# PCBDesign.net
KiCad netlist of a schematic drawn in EAGLE
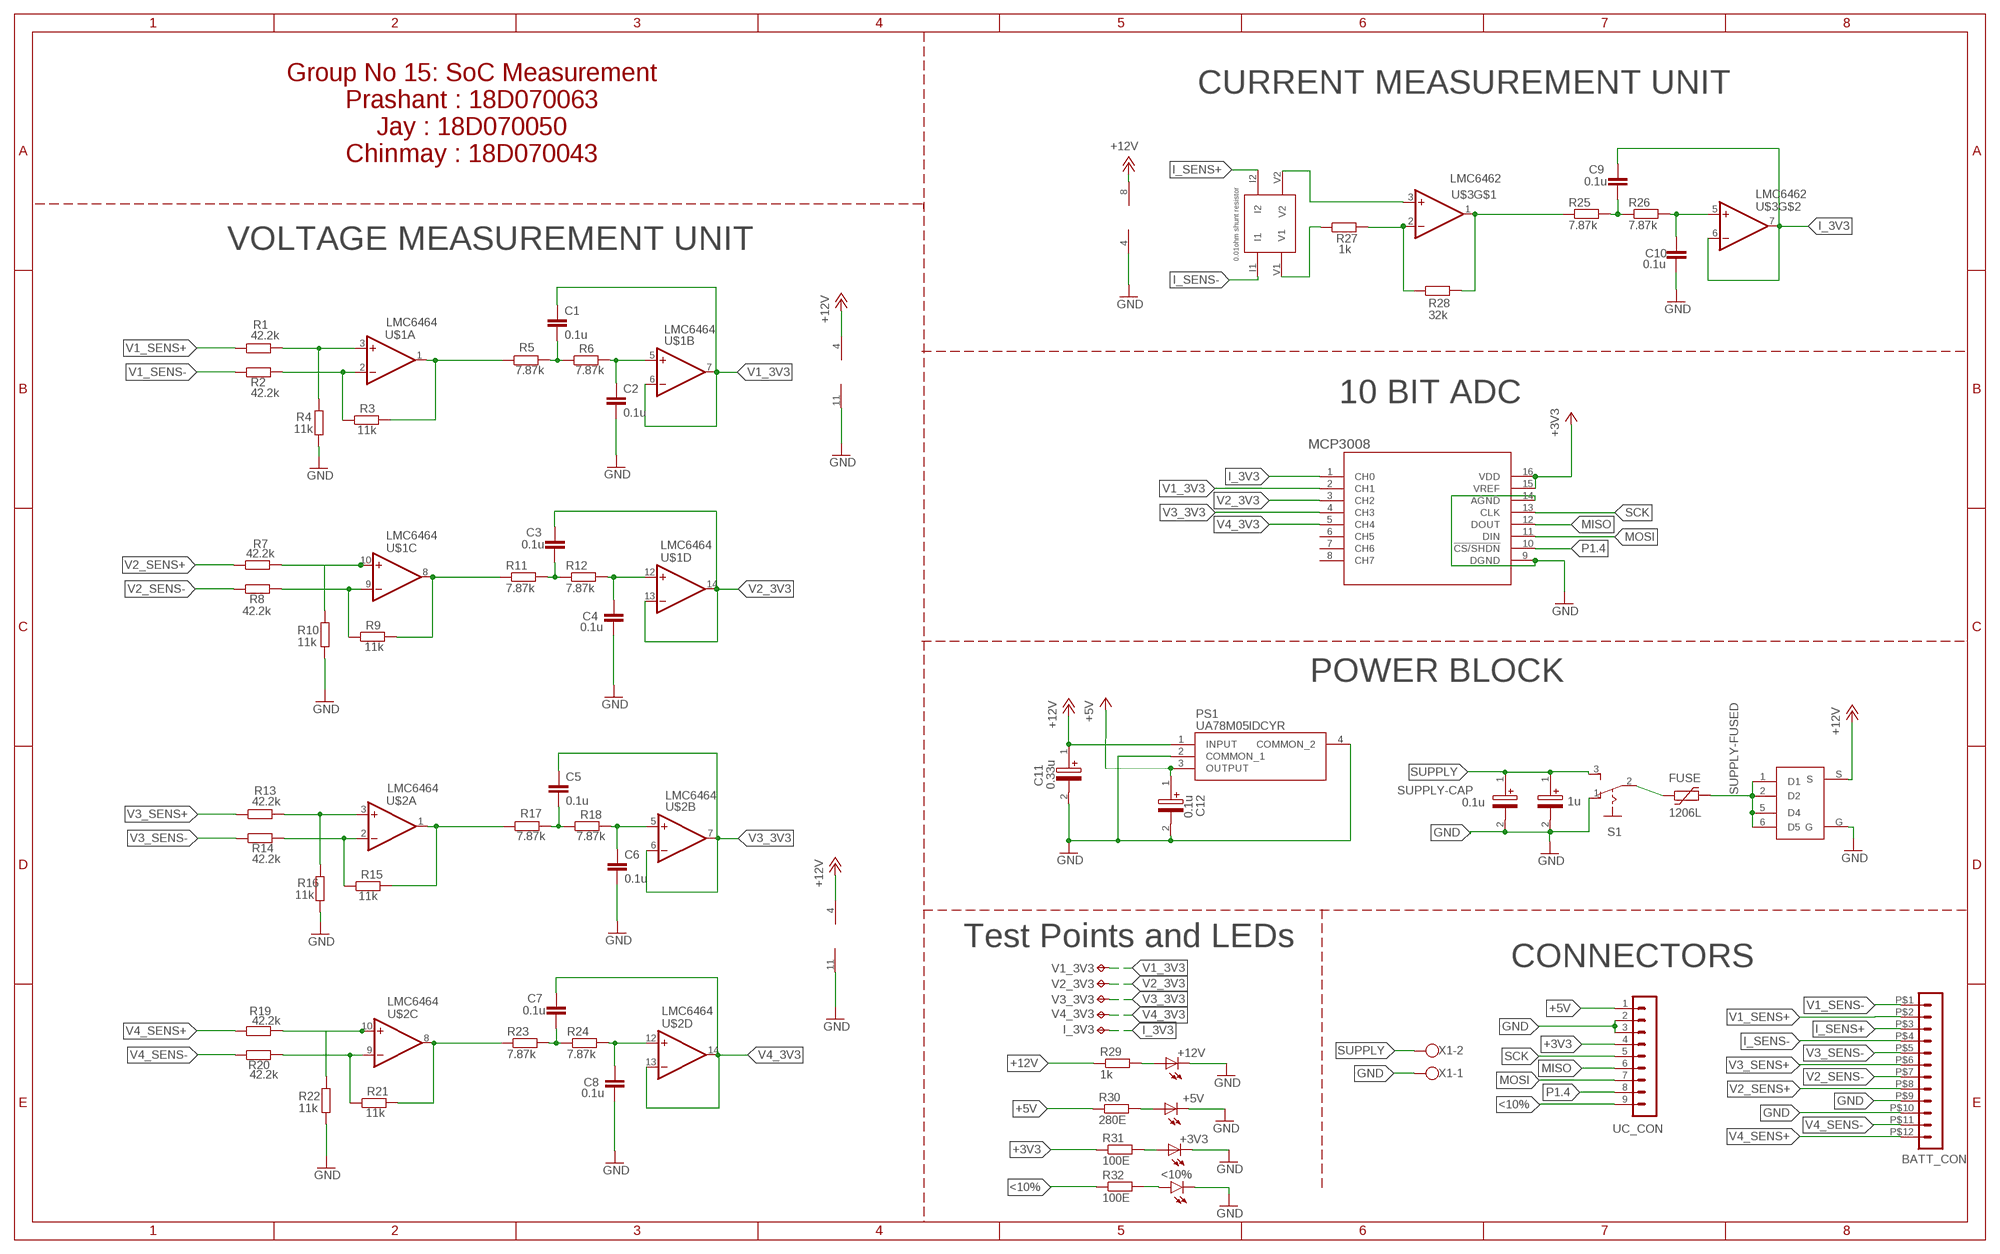
[diagram p0: schematic, sheet 1]

(export (version "E")
  (design (tool "Eeschema 10.0.6"))
  (components
    (comp (ref "+3V3")
      (value "LED-FKIT-1206")
      (footprint "eagle-import:FKIT-LED-1206")
      (libsource (lib "eagle-import") (part "LED-FKIT-1206"))
    )
    (comp (ref "+5V")
      (value "LED-FKIT-1206")
      (footprint "eagle-import:FKIT-LED-1206")
      (libsource (lib "eagle-import") (part "LED-FKIT-1206"))
    )
    (comp (ref "+12V")
      (value "LED-FKIT-1206")
      (footprint "eagle-import:FKIT-LED-1206")
      (libsource (lib "eagle-import") (part "LED-FKIT-1206"))
    )
    (comp (ref "<10%")
      (value "LED5MM")
      (footprint "eagle-import:LED5MM")
      (libsource (lib "eagle-import") (part "led_259_LED5MM"))
    )
    (comp (ref "BATT_CON")
      (value "HEADER_POS12_43045-1212")
      (footprint "eagle-import:43045-1212")
      (libsource (lib "eagle-import") (part "HEADER_POS12_?43045-1212"))
    )
    (comp (ref "C1")
      (value "0.1u")
      (footprint "eagle-import:C0805")
      (libsource (lib "eagle-import") (part "C-EUC0805"))
    )
    (comp (ref "C2")
      (value "0.1u")
      (footprint "eagle-import:C0805")
      (libsource (lib "eagle-import") (part "C-EUC0805"))
    )
    (comp (ref "C3")
      (value "0.1u")
      (footprint "eagle-import:C0805")
      (libsource (lib "eagle-import") (part "C-EUC0805"))
    )
    (comp (ref "C4")
      (value "0.1u")
      (footprint "eagle-import:C0805")
      (libsource (lib "eagle-import") (part "C-EUC0805"))
    )
    (comp (ref "C5")
      (value "0.1u")
      (footprint "eagle-import:C0805")
      (libsource (lib "eagle-import") (part "C-EUC0805"))
    )
    (comp (ref "C6")
      (value "0.1u")
      (footprint "eagle-import:C0805")
      (libsource (lib "eagle-import") (part "C-EUC0805"))
    )
    (comp (ref "C7")
      (value "0.1u")
      (footprint "eagle-import:C0805")
      (libsource (lib "eagle-import") (part "C-EUC0805"))
    )
    (comp (ref "C8")
      (value "0.1u")
      (footprint "eagle-import:C0805")
      (libsource (lib "eagle-import") (part "C-EUC0805"))
    )
    (comp (ref "C9")
      (value "0.1u")
      (footprint "eagle-import:C0805")
      (libsource (lib "eagle-import") (part "C-EUC0805"))
    )
    (comp (ref "C10")
      (value "0.1u")
      (footprint "eagle-import:C0805")
      (libsource (lib "eagle-import") (part "C-EUC0805"))
    )
    (comp (ref "C11")
      (value "0.33u")
      (footprint "eagle-import:CAPPM2014X120N")
      (fields
        (field (name "MANUFACTURER_PART_NUMBER") "TAJR334K020RNJ")
        (field (name "MOUSER_PART_NUMBER") "581-TAJR334K020R")
      )
      (libsource (lib "eagle-import") (part "TAJR334K020RNJ"))
    )
    (comp (ref "C12")
      (value "0.1u")
      (footprint "eagle-import:CAPPM2014X120N")
      (fields
        (field (name "MANUFACTURER_PART_NUMBER") "TAJR334K020RNJ")
        (field (name "MOUSER_PART_NUMBER") "581-TAJR334K020R")
      )
      (libsource (lib "eagle-import") (part "TAJR334K020RNJ"))
    )
    (comp (ref "FUSE")
      (value "1206L")
      (footprint "eagle-import:1206L")
      (fields (field (name "MFR") "Littelfuse"))
      (libsource (lib "eagle-import") (part "1206L"))
    )
    (comp (ref "I_3V3")
      (value "TESTPADPAD1-13")
      (footprint "eagle-import:P1-13")
      (libsource (lib "eagle-import") (part "TESTPADPAD1-13"))
    )
    (comp (ref "PS1")
      (value "UA78M05IDCYR")
      (footprint "eagle-import:SOT230P700X180-4N")
      (fields (field (name "MOUSER_PART_NUMBER") "595-UA78M05IDCYR"))
      (libsource (lib "eagle-import") (part "UA78M05IDCYR"))
    )
    (comp (ref "R1")
      (value "42.2k")
      (footprint "eagle-import:R0805")
      (libsource (lib "eagle-import") (part "IIT_BOMBAY_Racing2_R-EU_R0805"))
    )
    (comp (ref "R2")
      (value "42.2k")
      (footprint "eagle-import:R0805")
      (libsource (lib "eagle-import") (part "IIT_BOMBAY_Racing2_R-EU_R0805"))
    )
    (comp (ref "R3")
      (value "11k")
      (footprint "eagle-import:R0805")
      (libsource (lib "eagle-import") (part "IIT_BOMBAY_Racing2_R-EU_R0805"))
    )
    (comp (ref "R4")
      (value "11k")
      (footprint "eagle-import:R0805")
      (libsource (lib "eagle-import") (part "IIT_BOMBAY_Racing2_R-EU_R0805"))
    )
    (comp (ref "R5")
      (value "7.87k")
      (footprint "eagle-import:R0805")
      (libsource (lib "eagle-import") (part "IIT_BOMBAY_Racing2_R-EU_R0805"))
    )
    (comp (ref "R6")
      (value "7.87k")
      (footprint "eagle-import:R0805")
      (libsource (lib "eagle-import") (part "IIT_BOMBAY_Racing2_R-EU_R0805"))
    )
    (comp (ref "R7")
      (value "42.2k")
      (footprint "eagle-import:R0805")
      (libsource (lib "eagle-import") (part "IIT_BOMBAY_Racing2_R-EU_R0805"))
    )
    (comp (ref "R8")
      (value "42.2k")
      (footprint "eagle-import:R0805")
      (libsource (lib "eagle-import") (part "IIT_BOMBAY_Racing2_R-EU_R0805"))
    )
    (comp (ref "R9")
      (value "11k")
      (footprint "eagle-import:R0805")
      (libsource (lib "eagle-import") (part "IIT_BOMBAY_Racing2_R-EU_R0805"))
    )
    (comp (ref "R10")
      (value "11k")
      (footprint "eagle-import:R0805")
      (libsource (lib "eagle-import") (part "IIT_BOMBAY_Racing2_R-EU_R0805"))
    )
    (comp (ref "R11")
      (value "7.87k")
      (footprint "eagle-import:R0805")
      (libsource (lib "eagle-import") (part "IIT_BOMBAY_Racing2_R-EU_R0805"))
    )
    (comp (ref "R12")
      (value "7.87k")
      (footprint "eagle-import:R0805")
      (libsource (lib "eagle-import") (part "IIT_BOMBAY_Racing2_R-EU_R0805"))
    )
    (comp (ref "R13")
      (value "42.2k")
      (footprint "eagle-import:R0805")
      (libsource (lib "eagle-import") (part "IIT_BOMBAY_Racing2_R-EU_R0805"))
    )
    (comp (ref "R14")
      (value "42.2k")
      (footprint "eagle-import:R0805")
      (libsource (lib "eagle-import") (part "IIT_BOMBAY_Racing2_R-EU_R0805"))
    )
    (comp (ref "R15")
      (value "11k")
      (footprint "eagle-import:R0805")
      (libsource (lib "eagle-import") (part "IIT_BOMBAY_Racing2_R-EU_R0805"))
    )
    (comp (ref "R16")
      (value "11k")
      (footprint "eagle-import:R0805")
      (libsource (lib "eagle-import") (part "IIT_BOMBAY_Racing2_R-EU_R0805"))
    )
    (comp (ref "R17")
      (value "7.87k")
      (footprint "eagle-import:R0805")
      (libsource (lib "eagle-import") (part "IIT_BOMBAY_Racing2_R-EU_R0805"))
    )
    (comp (ref "R18")
      (value "7.87k")
      (footprint "eagle-import:R0805")
      (libsource (lib "eagle-import") (part "IIT_BOMBAY_Racing2_R-EU_R0805"))
    )
    (comp (ref "R19")
      (value "42.2k")
      (footprint "eagle-import:R0805")
      (libsource (lib "eagle-import") (part "IIT_BOMBAY_Racing2_R-EU_R0805"))
    )
    (comp (ref "R20")
      (value "42.2k")
      (footprint "eagle-import:R0805")
      (libsource (lib "eagle-import") (part "IIT_BOMBAY_Racing2_R-EU_R0805"))
    )
    (comp (ref "R21")
      (value "11k")
      (footprint "eagle-import:R0805")
      (libsource (lib "eagle-import") (part "IIT_BOMBAY_Racing2_R-EU_R0805"))
    )
    (comp (ref "R22")
      (value "11k")
      (footprint "eagle-import:R0805")
      (libsource (lib "eagle-import") (part "IIT_BOMBAY_Racing2_R-EU_R0805"))
    )
    (comp (ref "R23")
      (value "7.87k")
      (footprint "eagle-import:R0805")
      (libsource (lib "eagle-import") (part "IIT_BOMBAY_Racing2_R-EU_R0805"))
    )
    (comp (ref "R24")
      (value "7.87k")
      (footprint "eagle-import:R0805")
      (libsource (lib "eagle-import") (part "IIT_BOMBAY_Racing2_R-EU_R0805"))
    )
    (comp (ref "R25")
      (value "7.87k")
      (footprint "eagle-import:R0805")
      (libsource (lib "eagle-import") (part "IIT_BOMBAY_Racing2_R-EU_R0805"))
    )
    (comp (ref "R26")
      (value "7.87k")
      (footprint "eagle-import:R0805")
      (libsource (lib "eagle-import") (part "IIT_BOMBAY_Racing2_R-EU_R0805"))
    )
    (comp (ref "R27")
      (value "1k")
      (footprint "eagle-import:R0805")
      (libsource (lib "eagle-import") (part "IIT_BOMBAY_Racing2_R-EU_R0805"))
    )
    (comp (ref "R28")
      (value "32k")
      (footprint "eagle-import:R0805")
      (libsource (lib "eagle-import") (part "IIT_BOMBAY_Racing2_R-EU_R0805"))
    )
    (comp (ref "R29")
      (value "1k")
      (footprint "eagle-import:R0805")
      (libsource (lib "eagle-import") (part "R-EU_R0805"))
    )
    (comp (ref "R30")
      (value "280E")
      (footprint "eagle-import:R0805")
      (libsource (lib "eagle-import") (part "R-EU_R0805"))
    )
    (comp (ref "R31")
      (value "100E")
      (footprint "eagle-import:R0805")
      (libsource (lib "eagle-import") (part "R-EU_R0805"))
    )
    (comp (ref "R32")
      (value "100E")
      (footprint "eagle-import:R0805")
      (libsource (lib "eagle-import") (part "R-EU_R0805"))
    )
    (comp (ref "S1")
      (value "STS121PC04")
      (footprint "eagle-import:STS121PC04")
      (libsource (lib "eagle-import") (part "STS121PC04"))
    )
    (comp (ref "S2")
      (value "DMP3125L/SQ3419AEEV")
      (footprint "eagle-import:DMP3125L_SQ3419AEEV")
      (libsource (lib "eagle-import") (part "DMP3125L/SQ3419AEEV"))
    )
    (comp (ref "SUPPLY-CAP")
      (value "1u")
      (footprint "eagle-import:CAPPM2014X120N")
      (fields
        (field (name "MANUFACTURER_PART_NUMBER") "TAJR334K020RNJ")
        (field (name "MOUSER_PART_NUMBER") "581-TAJR334K020R")
      )
      (libsource (lib "eagle-import") (part "TAJR334K020RNJ"))
    )
    (comp (ref "SUPPLY-CAP1")
      (value "0.1u")
      (footprint "eagle-import:CAPPM2014X120N")
      (fields
        (field (name "MANUFACTURER_PART_NUMBER") "TAJR334K020RNJ")
        (field (name "MOUSER_PART_NUMBER") "581-TAJR334K020R")
      )
      (libsource (lib "eagle-import") (part "TAJR334K020RNJ"))
    )
    (comp (ref "U$1")
      (value "LMC6464")
      (footprint "eagle-import:SO14_LONGPADS")
      (libsource (lib "eagle-import") (part "LMC6464"))
    )
    (comp (ref "U$2")
      (value "LMC6464")
      (footprint "eagle-import:SO14_LONGPADS")
      (libsource (lib "eagle-import") (part "LMC6464"))
    )
    (comp (ref "U$3")
      (value "LMC6462")
      (footprint "eagle-import:S08")
      (libsource (lib "eagle-import") (part "LMC6462"))
    )
    (comp (ref "U$4")
      (value "0.01E")
      (footprint "eagle-import:SHNT_R_0.01")
      (libsource (lib "eagle-import") (part "0.01OHM_SHUNT_RESISTOR"))
    )
    (comp (ref "U1")
      (value "MCP3008")
      (footprint "eagle-import:SOIC16-N_MC_MCH-L")
      (fields
        (field (name "MANUFACTURER_PART_NUMBER") "MCP3008T-I/SL")
        (field (name "COPYRIGHT") "Copyright (C) 2018 Accelerated Designs. All rights reserved")
      )
      (libsource (lib "eagle-import") (part "MCP3008T-I/SLSOIC16-N_MC_MCH-L"))
    )
    (comp (ref "UC_CON")
      (value "MA09-1")
      (footprint "eagle-import:MA09-1")
      (libsource (lib "eagle-import") (part "MA09-1"))
    )
    (comp (ref "V1_3V3")
      (value "TESTPADPAD1-13")
      (footprint "eagle-import:P1-13")
      (libsource (lib "eagle-import") (part "TESTPADPAD1-13"))
    )
    (comp (ref "V2_3V3")
      (value "TESTPADPAD1-13")
      (footprint "eagle-import:P1-13")
      (libsource (lib "eagle-import") (part "TESTPADPAD1-13"))
    )
    (comp (ref "V3_3V3")
      (value "TESTPADPAD1-13")
      (footprint "eagle-import:P1-13")
      (libsource (lib "eagle-import") (part "TESTPADPAD1-13"))
    )
    (comp (ref "V4_3V3")
      (value "TESTPADPAD1-13")
      (footprint "eagle-import:P1-13")
      (libsource (lib "eagle-import") (part "TESTPADPAD1-13"))
    )
    (comp (ref "X1")
      (value "W237-102")
      (footprint "eagle-import:W237-102")
      (fields (field (name "MPN") "237-102"))
      (libsource (lib "eagle-import") (part "W237-102"))
    )
  )
  (nets
    (net (code "1") (name "+3V3") (class "Default")
      (node (ref "R31") (pin "1") (pinfunction "1_1") (pintype "passive"))
      (node (ref "U1") (pin "15") (pinfunction "VREF_15") (pintype "passive"))
      (node (ref "U1") (pin "16") (pinfunction "VDD_16") (pintype "passive"))
      (node (ref "UC_CON") (pin "4") (pinfunction "4_4") (pintype "passive"))
    )
    (net (code "2") (name "+5V") (class "Default")
      (node (ref "C12") (pin "1") (pinfunction "+_1") (pintype "bidirectional"))
      (node (ref "PS1") (pin "3") (pinfunction "OUTPUT_3") (pintype "bidirectional"))
      (node (ref "R30") (pin "1") (pinfunction "1_1") (pintype "passive"))
      (node (ref "UC_CON") (pin "1") (pinfunction "1_1") (pintype "passive"))
    )
    (net (code "3") (name "+12V") (class "Default")
      (node (ref "C11") (pin "1") (pinfunction "+_1") (pintype "bidirectional"))
      (node (ref "PS1") (pin "1") (pinfunction "INPUT_1") (pintype "bidirectional"))
      (node (ref "R29") (pin "1") (pinfunction "1_1") (pintype "passive"))
      (node (ref "S2") (pin "S") (pinfunction "S_S") (pintype "bidirectional"))
      (node (ref "U$1") (pin "4") (pinfunction "V+_4") (pintype "power_in"))
      (node (ref "U$2") (pin "4") (pinfunction "V+_4") (pintype "power_in"))
      (node (ref "U$3") (pin "8") (pinfunction "V+_8") (pintype "power_in"))
    )
    (net (code "4") (name "/SUPPLY-FUSED") (class "Default")
      (node (ref "FUSE") (pin "P$2") (pinfunction "2_P$2") (pintype "passive"))
      (node (ref "S2") (pin "1") (pinfunction "D1_1") (pintype "bidirectional"))
      (node (ref "S2") (pin "2") (pinfunction "D2_2") (pintype "bidirectional"))
      (node (ref "S2") (pin "5") (pinfunction "D4_5") (pintype "bidirectional"))
      (node (ref "S2") (pin "6") (pinfunction "D5_6") (pintype "bidirectional"))
    )
    (net (code "5") (name "<10%") (class "Default")
      (node (ref "R32") (pin "1") (pinfunction "1_1") (pintype "passive"))
      (node (ref "UC_CON") (pin "9") (pinfunction "9_9") (pintype "passive"))
    )
    (net (code "6") (name "GND") (class "Default")
      (node (ref "+12V") (pin "C") (pinfunction "C_C") (pintype "passive"))
      (node (ref "+3V3") (pin "C") (pinfunction "C_C") (pintype "passive"))
      (node (ref "+5V") (pin "C") (pinfunction "C_C") (pintype "passive"))
      (node (ref "<10%") (pin "K") (pinfunction "C_K") (pintype "passive"))
      (node (ref "BATT_CON") (pin "P$10") (pinfunction "10_P$10") (pintype "passive"))
      (node (ref "BATT_CON") (pin "P$9") (pinfunction "9_P$9") (pintype "passive"))
      (node (ref "C10") (pin "2") (pinfunction "2_2") (pintype "passive"))
      (node (ref "C11") (pin "2") (pinfunction "-_2") (pintype "bidirectional"))
      (node (ref "C12") (pin "2") (pinfunction "-_2") (pintype "bidirectional"))
      (node (ref "C2") (pin "2") (pinfunction "2_2") (pintype "passive"))
      (node (ref "C4") (pin "2") (pinfunction "2_2") (pintype "passive"))
      (node (ref "C6") (pin "2") (pinfunction "2_2") (pintype "passive"))
      (node (ref "C8") (pin "2") (pinfunction "2_2") (pintype "passive"))
      (node (ref "PS1") (pin "2") (pinfunction "COMMON_1_2") (pintype "bidirectional"))
      (node (ref "PS1") (pin "4") (pinfunction "COMMON_2_4") (pintype "bidirectional"))
      (node (ref "R10") (pin "2") (pinfunction "2_2") (pintype "passive"))
      (node (ref "R16") (pin "2") (pinfunction "2_2") (pintype "passive"))
      (node (ref "R22") (pin "2") (pinfunction "2_2") (pintype "passive"))
      (node (ref "R4") (pin "2") (pinfunction "2_2") (pintype "passive"))
      (node (ref "S1") (pin "1") (pinfunction "O_1") (pintype "passive"))
      (node (ref "S2") (pin "G") (pinfunction "G_G") (pintype "bidirectional"))
      (node (ref "SUPPLY-CAP") (pin "2") (pinfunction "-_2") (pintype "bidirectional"))
      (node (ref "SUPPLY-CAP1") (pin "2") (pinfunction "-_2") (pintype "bidirectional"))
      (node (ref "U$1") (pin "11") (pinfunction "V-_11") (pintype "power_in"))
      (node (ref "U$2") (pin "11") (pinfunction "V-_11") (pintype "power_in"))
      (node (ref "U$3") (pin "4") (pinfunction "V-_4") (pintype "power_in"))
      (node (ref "U1") (pin "14") (pinfunction "AGND_14") (pintype "passive"))
      (node (ref "U1") (pin "9") (pinfunction "DGND_9") (pintype "passive"))
      (node (ref "UC_CON") (pin "2") (pinfunction "2_2") (pintype "passive"))
      (node (ref "UC_CON") (pin "3") (pinfunction "3_3") (pintype "passive"))
      (node (ref "X1") (pin "1") (pinfunction "KL_1") (pintype "passive"))
    )
    (net (code "7") (name "I_3V3") (class "Default")
      (node (ref "C9") (pin "1") (pinfunction "1_1") (pintype "passive"))
      (node (ref "I_3V3") (pin "TP") (pinfunction "TP_TP") (pintype "input"))
      (node (ref "U$3") (pin "6") (pinfunction "-IN_6") (pintype "input"))
      (node (ref "U$3") (pin "7") (pinfunction "OUT_7") (pintype "output"))
      (node (ref "U1") (pin "1") (pinfunction "CH0_1") (pintype "passive"))
    )
    (net (code "8") (name "I_SENS+") (class "Default")
      (node (ref "BATT_CON") (pin "P$3") (pinfunction "3_P$3") (pintype "passive"))
      (node (ref "U$4") (pin "I2") (pinfunction "I2_I2") (pintype "bidirectional"))
    )
    (net (code "9") (name "I_SENS-") (class "Default")
      (node (ref "BATT_CON") (pin "P$4") (pinfunction "4_P$4") (pintype "passive"))
      (node (ref "U$4") (pin "I1") (pinfunction "I1_I1") (pintype "bidirectional"))
    )
    (net (code "10") (name "MISO") (class "Default")
      (node (ref "U1") (pin "12") (pinfunction "DOUT_12") (pintype "passive"))
      (node (ref "UC_CON") (pin "6") (pinfunction "6_6") (pintype "passive"))
    )
    (net (code "11") (name "MOSI") (class "Default")
      (node (ref "U1") (pin "11") (pinfunction "DIN_11") (pintype "passive"))
      (node (ref "UC_CON") (pin "7") (pinfunction "7_7") (pintype "passive"))
    )
    (net (code "12") (name "Net-(+3V3-PadA)") (class "Default")
      (node (ref "+3V3") (pin "A") (pinfunction "A_A") (pintype "passive"))
      (node (ref "R31") (pin "2") (pinfunction "2_2") (pintype "passive"))
    )
    (net (code "13") (name "Net-(+5V-PadA)") (class "Default")
      (node (ref "+5V") (pin "A") (pinfunction "A_A") (pintype "passive"))
      (node (ref "R30") (pin "2") (pinfunction "2_2") (pintype "passive"))
    )
    (net (code "14") (name "Net-(+12V-PadA)") (class "Default")
      (node (ref "+12V") (pin "A") (pinfunction "A_A") (pintype "passive"))
      (node (ref "R29") (pin "2") (pinfunction "2_2") (pintype "passive"))
    )
    (net (code "15") (name "Net-(<10%-PadA)") (class "Default")
      (node (ref "<10%") (pin "A") (pinfunction "A_A") (pintype "passive"))
      (node (ref "R32") (pin "2") (pinfunction "2_2") (pintype "passive"))
    )
    (net (code "16") (name "Net-(C1-Pad2)") (class "Default")
      (node (ref "C1") (pin "2") (pinfunction "2_2") (pintype "passive"))
      (node (ref "R5") (pin "2") (pinfunction "2_2") (pintype "passive"))
      (node (ref "R6") (pin "1") (pinfunction "1_1") (pintype "passive"))
    )
    (net (code "17") (name "Net-(C3-Pad2)") (class "Default")
      (node (ref "C3") (pin "2") (pinfunction "2_2") (pintype "passive"))
      (node (ref "R11") (pin "2") (pinfunction "2_2") (pintype "passive"))
      (node (ref "R12") (pin "1") (pinfunction "1_1") (pintype "passive"))
    )
    (net (code "18") (name "Net-(C5-Pad2)") (class "Default")
      (node (ref "C5") (pin "2") (pinfunction "2_2") (pintype "passive"))
      (node (ref "R17") (pin "2") (pinfunction "2_2") (pintype "passive"))
      (node (ref "R18") (pin "1") (pinfunction "1_1") (pintype "passive"))
    )
    (net (code "19") (name "Net-(C7-Pad2)") (class "Default")
      (node (ref "C7") (pin "2") (pinfunction "2_2") (pintype "passive"))
      (node (ref "R23") (pin "2") (pinfunction "2_2") (pintype "passive"))
      (node (ref "R24") (pin "1") (pinfunction "1_1") (pintype "passive"))
    )
    (net (code "20") (name "Net-(C9-Pad2)") (class "Default")
      (node (ref "C9") (pin "2") (pinfunction "2_2") (pintype "passive"))
      (node (ref "R25") (pin "2") (pinfunction "2_2") (pintype "passive"))
      (node (ref "R26") (pin "1") (pinfunction "1_1") (pintype "passive"))
    )
    (net (code "21") (name "Net-(FUSE-1)") (class "Default")
      (node (ref "FUSE") (pin "P$1") (pinfunction "1_P$1") (pintype "passive"))
      (node (ref "S1") (pin "2") (pinfunction "P_2") (pintype "passive"))
    )
    (net (code "22") (name "Net-(R27-Pad1)") (class "Default")
      (node (ref "R27") (pin "1") (pinfunction "1_1") (pintype "passive"))
      (node (ref "U$4") (pin "V1") (pinfunction "V1_V1") (pintype "bidirectional"))
    )
    (net (code "23") (name "Net-(U$1A-+IN)") (class "Default")
      (node (ref "R1") (pin "2") (pinfunction "2_2") (pintype "passive"))
      (node (ref "R4") (pin "1") (pinfunction "1_1") (pintype "passive"))
      (node (ref "U$1") (pin "3") (pinfunction "+IN_3") (pintype "input"))
    )
    (net (code "24") (name "Net-(U$1A--IN)") (class "Default")
      (node (ref "R2") (pin "2") (pinfunction "2_2") (pintype "passive"))
      (node (ref "R3") (pin "1") (pinfunction "1_1") (pintype "passive"))
      (node (ref "U$1") (pin "2") (pinfunction "-IN_2") (pintype "input"))
    )
    (net (code "25") (name "Net-(U$1A-OUT)") (class "Default")
      (node (ref "R3") (pin "2") (pinfunction "2_2") (pintype "passive"))
      (node (ref "R5") (pin "1") (pinfunction "1_1") (pintype "passive"))
      (node (ref "U$1") (pin "1") (pinfunction "OUT_1") (pintype "output"))
    )
    (net (code "26") (name "Net-(U$1B-+IN)") (class "Default")
      (node (ref "C2") (pin "1") (pinfunction "1_1") (pintype "passive"))
      (node (ref "R6") (pin "2") (pinfunction "2_2") (pintype "passive"))
      (node (ref "U$1") (pin "5") (pinfunction "+IN_5") (pintype "input"))
    )
    (net (code "27") (name "Net-(U$1C-+IN)") (class "Default")
      (node (ref "R10") (pin "1") (pinfunction "1_1") (pintype "passive"))
      (node (ref "R7") (pin "2") (pinfunction "2_2") (pintype "passive"))
      (node (ref "U$1") (pin "10") (pinfunction "+IN_10") (pintype "input"))
    )
    (net (code "28") (name "Net-(U$1C--IN)") (class "Default")
      (node (ref "R8") (pin "2") (pinfunction "2_2") (pintype "passive"))
      (node (ref "R9") (pin "1") (pinfunction "1_1") (pintype "passive"))
      (node (ref "U$1") (pin "9") (pinfunction "-IN_9") (pintype "input"))
    )
    (net (code "29") (name "Net-(U$1C-OUT)") (class "Default")
      (node (ref "R11") (pin "1") (pinfunction "1_1") (pintype "passive"))
      (node (ref "R9") (pin "2") (pinfunction "2_2") (pintype "passive"))
      (node (ref "U$1") (pin "8") (pinfunction "OUT_8") (pintype "output"))
    )
    (net (code "30") (name "Net-(U$1D-+IN)") (class "Default")
      (node (ref "C4") (pin "1") (pinfunction "1_1") (pintype "passive"))
      (node (ref "R12") (pin "2") (pinfunction "2_2") (pintype "passive"))
      (node (ref "U$1") (pin "12") (pinfunction "+IN_12") (pintype "input"))
    )
    (net (code "31") (name "Net-(U$2A-+IN)") (class "Default")
      (node (ref "R13") (pin "2") (pinfunction "2_2") (pintype "passive"))
      (node (ref "R16") (pin "1") (pinfunction "1_1") (pintype "passive"))
      (node (ref "U$2") (pin "3") (pinfunction "+IN_3") (pintype "input"))
    )
    (net (code "32") (name "Net-(U$2A--IN)") (class "Default")
      (node (ref "R14") (pin "2") (pinfunction "2_2") (pintype "passive"))
      (node (ref "R15") (pin "1") (pinfunction "1_1") (pintype "passive"))
      (node (ref "U$2") (pin "2") (pinfunction "-IN_2") (pintype "input"))
    )
    (net (code "33") (name "Net-(U$2A-OUT)") (class "Default")
      (node (ref "R15") (pin "2") (pinfunction "2_2") (pintype "passive"))
      (node (ref "R17") (pin "1") (pinfunction "1_1") (pintype "passive"))
      (node (ref "U$2") (pin "1") (pinfunction "OUT_1") (pintype "output"))
    )
    (net (code "34") (name "Net-(U$2B-+IN)") (class "Default")
      (node (ref "C6") (pin "1") (pinfunction "1_1") (pintype "passive"))
      (node (ref "R18") (pin "2") (pinfunction "2_2") (pintype "passive"))
      (node (ref "U$2") (pin "5") (pinfunction "+IN_5") (pintype "input"))
    )
    (net (code "35") (name "Net-(U$2C-+IN)") (class "Default")
      (node (ref "R19") (pin "2") (pinfunction "2_2") (pintype "passive"))
      (node (ref "R22") (pin "1") (pinfunction "1_1") (pintype "passive"))
      (node (ref "U$2") (pin "10") (pinfunction "+IN_10") (pintype "input"))
    )
    (net (code "36") (name "Net-(U$2C--IN)") (class "Default")
      (node (ref "R20") (pin "2") (pinfunction "2_2") (pintype "passive"))
      (node (ref "R21") (pin "1") (pinfunction "1_1") (pintype "passive"))
      (node (ref "U$2") (pin "9") (pinfunction "-IN_9") (pintype "input"))
    )
    (net (code "37") (name "Net-(U$2C-OUT)") (class "Default")
      (node (ref "R21") (pin "2") (pinfunction "2_2") (pintype "passive"))
      (node (ref "R23") (pin "1") (pinfunction "1_1") (pintype "passive"))
      (node (ref "U$2") (pin "8") (pinfunction "OUT_8") (pintype "output"))
    )
    (net (code "38") (name "Net-(U$2D-+IN)") (class "Default")
      (node (ref "C8") (pin "1") (pinfunction "1_1") (pintype "passive"))
      (node (ref "R24") (pin "2") (pinfunction "2_2") (pintype "passive"))
      (node (ref "U$2") (pin "12") (pinfunction "+IN_12") (pintype "input"))
    )
    (net (code "39") (name "Net-(U$3A-+IN)") (class "Default")
      (node (ref "U$3") (pin "3") (pinfunction "+IN_3") (pintype "input"))
      (node (ref "U$4") (pin "V2") (pinfunction "V2_V2") (pintype "bidirectional"))
    )
    (net (code "40") (name "Net-(U$3A--IN)") (class "Default")
      (node (ref "R27") (pin "2") (pinfunction "2_2") (pintype "passive"))
      (node (ref "R28") (pin "1") (pinfunction "1_1") (pintype "passive"))
      (node (ref "U$3") (pin "2") (pinfunction "-IN_2") (pintype "input"))
    )
    (net (code "41") (name "Net-(U$3A-OUT)") (class "Default")
      (node (ref "R25") (pin "1") (pinfunction "1_1") (pintype "passive"))
      (node (ref "R28") (pin "2") (pinfunction "2_2") (pintype "passive"))
      (node (ref "U$3") (pin "1") (pinfunction "OUT_1") (pintype "output"))
    )
    (net (code "42") (name "Net-(U$3B-+IN)") (class "Default")
      (node (ref "C10") (pin "1") (pinfunction "1_1") (pintype "passive"))
      (node (ref "R26") (pin "2") (pinfunction "2_2") (pintype "passive"))
      (node (ref "U$3") (pin "5") (pinfunction "+IN_5") (pintype "input"))
    )
    (net (code "43") (name "P1.4") (class "Default")
      (node (ref "U1") (pin "10") (pinfunction "~{CS/SHDN}_10") (pintype "passive"))
      (node (ref "UC_CON") (pin "8") (pinfunction "8_8") (pintype "passive"))
    )
    (net (code "44") (name "SCK") (class "Default")
      (node (ref "U1") (pin "13") (pinfunction "CLK_13") (pintype "passive"))
      (node (ref "UC_CON") (pin "5") (pinfunction "5_5") (pintype "passive"))
    )
    (net (code "45") (name "SUPPLY") (class "Default")
      (node (ref "S1") (pin "3") (pinfunction "S_3") (pintype "passive"))
      (node (ref "SUPPLY-CAP") (pin "1") (pinfunction "+_1") (pintype "bidirectional"))
      (node (ref "SUPPLY-CAP1") (pin "1") (pinfunction "+_1") (pintype "bidirectional"))
      (node (ref "X1") (pin "2") (pinfunction "KL_2") (pintype "passive"))
    )
    (net (code "46") (name "V1_3V3") (class "Default")
      (node (ref "C1") (pin "1") (pinfunction "1_1") (pintype "passive"))
      (node (ref "U$1") (pin "6") (pinfunction "-IN_6") (pintype "input"))
      (node (ref "U$1") (pin "7") (pinfunction "OUT_7") (pintype "output"))
      (node (ref "U1") (pin "2") (pinfunction "CH1_2") (pintype "passive"))
      (node (ref "V1_3V3") (pin "TP") (pinfunction "TP_TP") (pintype "input"))
    )
    (net (code "47") (name "V1_SENS+") (class "Default")
      (node (ref "BATT_CON") (pin "P$2") (pinfunction "2_P$2") (pintype "passive"))
      (node (ref "R1") (pin "1") (pinfunction "1_1") (pintype "passive"))
    )
    (net (code "48") (name "V1_SENS-") (class "Default")
      (node (ref "BATT_CON") (pin "P$1") (pinfunction "1_P$1") (pintype "passive"))
      (node (ref "R2") (pin "1") (pinfunction "1_1") (pintype "passive"))
    )
    (net (code "49") (name "V2_3V3") (class "Default")
      (node (ref "C3") (pin "1") (pinfunction "1_1") (pintype "passive"))
      (node (ref "U$1") (pin "13") (pinfunction "-IN_13") (pintype "input"))
      (node (ref "U$1") (pin "14") (pinfunction "OUT_14") (pintype "output"))
      (node (ref "U1") (pin "3") (pinfunction "CH2_3") (pintype "passive"))
      (node (ref "V2_3V3") (pin "TP") (pinfunction "TP_TP") (pintype "input"))
    )
    (net (code "50") (name "V2_SENS+") (class "Default")
      (node (ref "BATT_CON") (pin "P$8") (pinfunction "8_P$8") (pintype "passive"))
      (node (ref "R7") (pin "1") (pinfunction "1_1") (pintype "passive"))
    )
    (net (code "51") (name "V2_SENS-") (class "Default")
      (node (ref "BATT_CON") (pin "P$7") (pinfunction "7_P$7") (pintype "passive"))
      (node (ref "R8") (pin "1") (pinfunction "1_1") (pintype "passive"))
    )
    (net (code "52") (name "V3_3V3") (class "Default")
      (node (ref "C5") (pin "1") (pinfunction "1_1") (pintype "passive"))
      (node (ref "U$2") (pin "6") (pinfunction "-IN_6") (pintype "input"))
      (node (ref "U$2") (pin "7") (pinfunction "OUT_7") (pintype "output"))
      (node (ref "U1") (pin "4") (pinfunction "CH3_4") (pintype "passive"))
      (node (ref "V3_3V3") (pin "TP") (pinfunction "TP_TP") (pintype "input"))
    )
    (net (code "53") (name "V3_SENS+") (class "Default")
      (node (ref "BATT_CON") (pin "P$6") (pinfunction "6_P$6") (pintype "passive"))
      (node (ref "R13") (pin "1") (pinfunction "1_1") (pintype "passive"))
    )
    (net (code "54") (name "V3_SENS-") (class "Default")
      (node (ref "BATT_CON") (pin "P$5") (pinfunction "5_P$5") (pintype "passive"))
      (node (ref "R14") (pin "1") (pinfunction "1_1") (pintype "passive"))
    )
    (net (code "55") (name "V4_3V3") (class "Default")
      (node (ref "C7") (pin "1") (pinfunction "1_1") (pintype "passive"))
      (node (ref "U$2") (pin "13") (pinfunction "-IN_13") (pintype "input"))
      (node (ref "U$2") (pin "14") (pinfunction "OUT_14") (pintype "output"))
      (node (ref "U1") (pin "5") (pinfunction "CH4_5") (pintype "passive"))
      (node (ref "V4_3V3") (pin "TP") (pinfunction "TP_TP") (pintype "input"))
    )
    (net (code "56") (name "V4_SENS+") (class "Default")
      (node (ref "BATT_CON") (pin "P$12") (pinfunction "12_P$12") (pintype "passive"))
      (node (ref "R19") (pin "1") (pinfunction "1_1") (pintype "passive"))
    )
    (net (code "57") (name "V4_SENS-") (class "Default")
      (node (ref "BATT_CON") (pin "P$11") (pinfunction "11_P$11") (pintype "passive"))
      (node (ref "R20") (pin "1") (pinfunction "1_1") (pintype "passive"))
    )
    (net (code "58") (name "unconnected-(U1-CH5-Pad6)") (class "Default")
      (node (ref "U1") (pin "6") (pinfunction "CH5_6") (pintype "passive"))
    )
    (net (code "59") (name "unconnected-(U1-CH6-Pad7)") (class "Default")
      (node (ref "U1") (pin "7") (pinfunction "CH6_7") (pintype "passive"))
    )
    (net (code "60") (name "unconnected-(U1-CH7-Pad8)") (class "Default")
      (node (ref "U1") (pin "8") (pinfunction "CH7_8") (pintype "passive"))
    )
  )
)
